# ButtonBoard.net
KiCad netlist of a schematic drawn in EAGLE
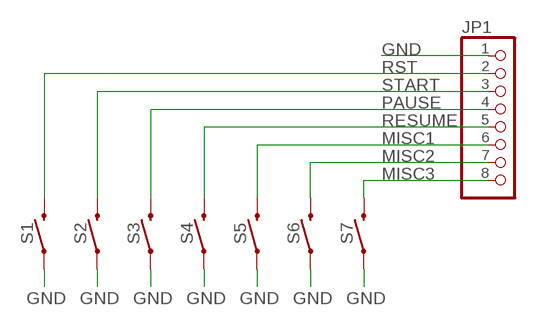
[diagram p0: schematic, sheet 1]

(export (version "E")
  (design (tool "Eeschema 10.0.6"))
  (components
    (comp (ref "JP1")
      (value "PINHD-1X8/90")
      (footprint "eagle-import:1X08_90")
      (libsource (lib "eagle-import") (part "PINHD-1X8/90"))
    )
    (comp (ref "S1")
      (value "MOMENTARY-SWITCH-SPST-SMD-12MM")
      (footprint "eagle-import:TACTILE_SWITCH_SMD_12MM")
      (libsource (lib "eagle-import") (part "MOMENTARY-SWITCH-SPST-SMD-12MM"))
    )
    (comp (ref "S2")
      (value "MOMENTARY-SWITCH-SPST-SMD-12MM")
      (footprint "eagle-import:TACTILE_SWITCH_SMD_12MM")
      (libsource (lib "eagle-import") (part "MOMENTARY-SWITCH-SPST-SMD-12MM"))
    )
    (comp (ref "S3")
      (value "MOMENTARY-SWITCH-SPST-SMD-12MM")
      (footprint "eagle-import:TACTILE_SWITCH_SMD_12MM")
      (libsource (lib "eagle-import") (part "MOMENTARY-SWITCH-SPST-SMD-12MM"))
    )
    (comp (ref "S4")
      (value "MOMENTARY-SWITCH-SPST-SMD-12MM")
      (footprint "eagle-import:TACTILE_SWITCH_SMD_12MM")
      (libsource (lib "eagle-import") (part "MOMENTARY-SWITCH-SPST-SMD-12MM"))
    )
    (comp (ref "S5")
      (value "MOMENTARY-SWITCH-SPST-SMD-12MM")
      (footprint "eagle-import:TACTILE_SWITCH_SMD_12MM")
      (libsource (lib "eagle-import") (part "MOMENTARY-SWITCH-SPST-SMD-12MM"))
    )
    (comp (ref "S6")
      (value "MOMENTARY-SWITCH-SPST-SMD-12MM")
      (footprint "eagle-import:TACTILE_SWITCH_SMD_12MM")
      (libsource (lib "eagle-import") (part "MOMENTARY-SWITCH-SPST-SMD-12MM"))
    )
    (comp (ref "S7")
      (value "MOMENTARY-SWITCH-SPST-SMD-12MM")
      (footprint "eagle-import:TACTILE_SWITCH_SMD_12MM")
      (libsource (lib "eagle-import") (part "MOMENTARY-SWITCH-SPST-SMD-12MM"))
    )
  )
  (nets
    (net (code "1") (name "/GND") (class "Default")
      (node (ref "JP1") (pin "1") (pinfunction "1_1") (pintype "passive"))
      (node (ref "S1") (pin "1") (pinfunction "1_1") (pintype "passive"))
      (node (ref "S2") (pin "1") (pinfunction "1_1") (pintype "passive"))
      (node (ref "S3") (pin "1") (pinfunction "1_1") (pintype "passive"))
      (node (ref "S4") (pin "1") (pinfunction "1_1") (pintype "passive"))
      (node (ref "S5") (pin "1") (pinfunction "1_1") (pintype "passive"))
      (node (ref "S6") (pin "1") (pinfunction "1_1") (pintype "passive"))
      (node (ref "S7") (pin "1") (pinfunction "1_1") (pintype "passive"))
    )
    (net (code "2") (name "/MISC1") (class "Default")
      (node (ref "JP1") (pin "6") (pinfunction "6_6") (pintype "passive"))
      (node (ref "S5") (pin "3") (pinfunction "2_3") (pintype "passive"))
    )
    (net (code "3") (name "/MISC2") (class "Default")
      (node (ref "JP1") (pin "7") (pinfunction "7_7") (pintype "passive"))
      (node (ref "S6") (pin "3") (pinfunction "2_3") (pintype "passive"))
    )
    (net (code "4") (name "/MISC3") (class "Default")
      (node (ref "JP1") (pin "8") (pinfunction "8_8") (pintype "passive"))
      (node (ref "S7") (pin "3") (pinfunction "2_3") (pintype "passive"))
    )
    (net (code "5") (name "/PAUSE") (class "Default")
      (node (ref "JP1") (pin "4") (pinfunction "4_4") (pintype "passive"))
      (node (ref "S3") (pin "3") (pinfunction "2_3") (pintype "passive"))
    )
    (net (code "6") (name "/RESUME") (class "Default")
      (node (ref "JP1") (pin "5") (pinfunction "5_5") (pintype "passive"))
      (node (ref "S4") (pin "3") (pinfunction "2_3") (pintype "passive"))
    )
    (net (code "7") (name "/RST") (class "Default")
      (node (ref "JP1") (pin "2") (pinfunction "2_2") (pintype "passive"))
      (node (ref "S1") (pin "3") (pinfunction "2_3") (pintype "passive"))
    )
    (net (code "8") (name "/START") (class "Default")
      (node (ref "JP1") (pin "3") (pinfunction "3_3") (pintype "passive"))
      (node (ref "S2") (pin "3") (pinfunction "2_3") (pintype "passive"))
    )
  )
)
